# power_supply.net
KiCad netlist of a schematic drawn in Altium Designer
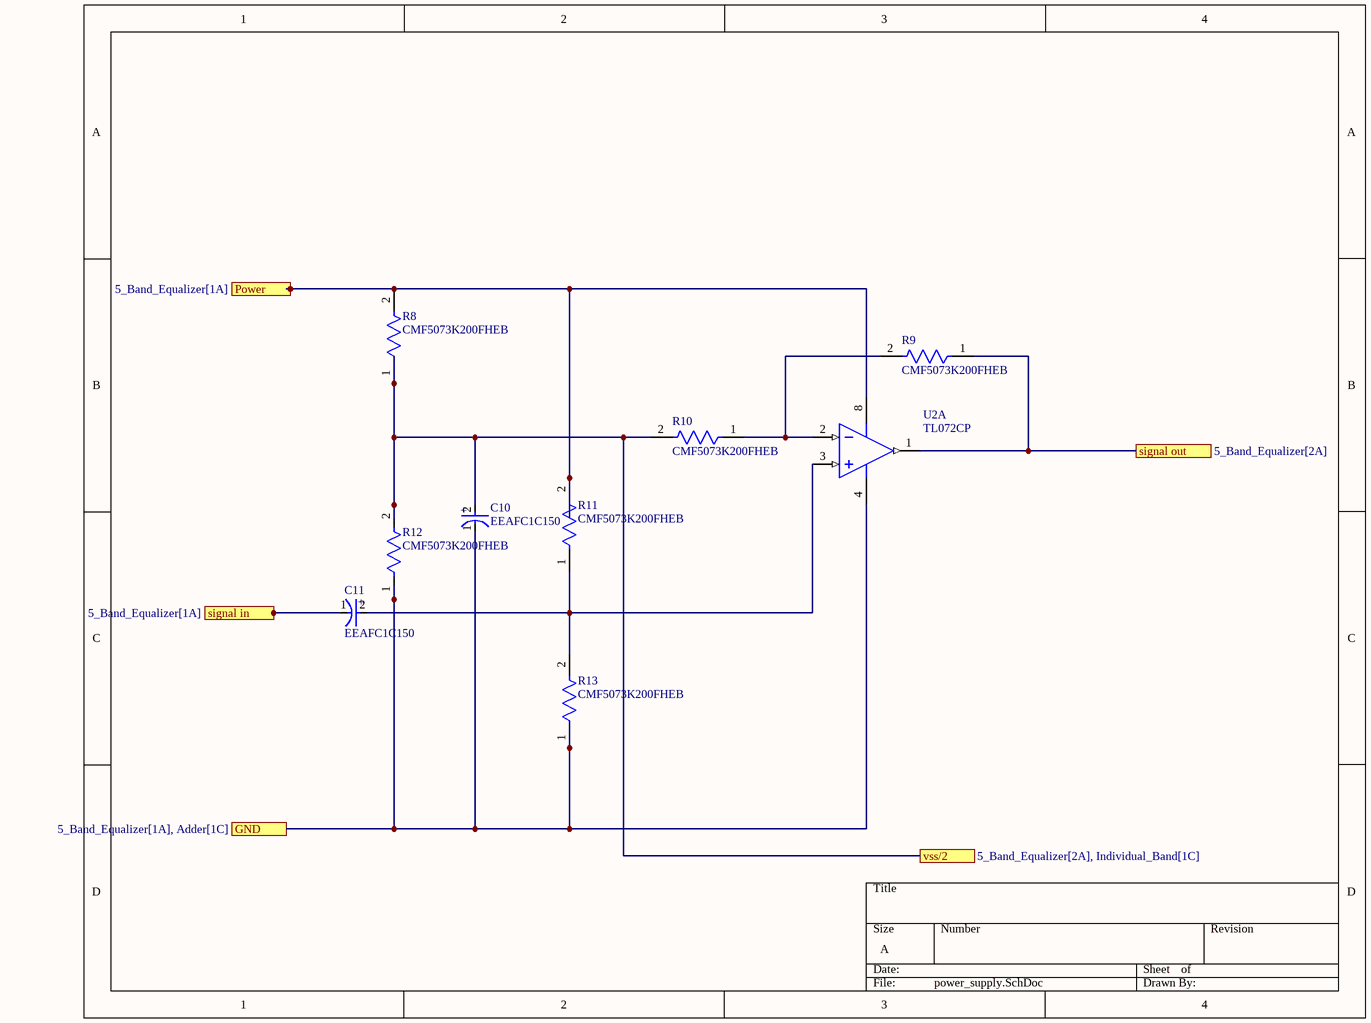
[diagram p0: power_supply.SchDoc]

(export (version "E")
  (design (tool "Eeschema 10.0.6"))
  (components
    (comp (ref "C10")
      (value "EEAFC1C150")
      (footprint "FP-RAD-TH-D_4_0_5-L_7_1-F-MFG")
      (description "Aluminum Electrolytic Capacitors (Radial Lead Type) AEC-Q200 Qualified 15uF ±20% 16V")
      (fields (field (name "VOLTAGE") "16V") (field (name "TOLERANCE") "20%"))
      (libsource (lib "Altium Content Vault") (part "a00bbbee19879c290e62620ae7e47b1"))
    )
    (comp (ref "C11")
      (value "EEAFC1C150")
      (footprint "FP-RAD-TH-D_4_0_5-L_7_1-F-MFG")
      (description "Aluminum Electrolytic Capacitors (Radial Lead Type) AEC-Q200 Qualified 15uF ±20% 16V")
      (fields (field (name "VOLTAGE") "16V") (field (name "TOLERANCE") "20%"))
      (libsource (lib "Altium Content Vault") (part "a00bbbee19879c290e62620ae7e47b1"))
    )
    (comp (ref "R8")
      (value "CMF5073K200FHEB")
      (footprint "FP-CMF50-0")
      (description "CMF5073K200FHEB Res Metal Film 73.2K Ohm 1% 0.125W(1/8W) ±50ppm/°C Epoxy AXL T/R")
      (fields (field (name "TOLERANCE") "1%"))
      (libsource (lib "Altium Content Vault") (part "1029c3af85768c4190bb7ad29bc67b5"))
    )
    (comp (ref "R9")
      (value "CMF5073K200FHEB")
      (footprint "FP-CMF50-0")
      (description "CMF5073K200FHEB Res Metal Film 73.2K Ohm 1% 0.125W(1/8W) ±50ppm/°C Epoxy AXL T/R")
      (fields (field (name "TOLERANCE") "1%"))
      (libsource (lib "Altium Content Vault") (part "1029c3af85768c4190bb7ad29bc67b5"))
    )
    (comp (ref "R10")
      (value "CMF5073K200FHEB")
      (footprint "FP-CMF50-0")
      (description "CMF5073K200FHEB Res Metal Film 73.2K Ohm 1% 0.125W(1/8W) ±50ppm/°C Epoxy AXL T/R")
      (fields (field (name "TOLERANCE") "1%"))
      (libsource (lib "Altium Content Vault") (part "1029c3af85768c4190bb7ad29bc67b5"))
    )
    (comp (ref "R11")
      (value "CMF5073K200FHEB")
      (footprint "FP-CMF50-0")
      (description "CMF5073K200FHEB Res Metal Film 73.2K Ohm 1% 0.125W(1/8W) ±50ppm/°C Epoxy AXL T/R")
      (fields (field (name "TOLERANCE") "1%"))
      (libsource (lib "Altium Content Vault") (part "1029c3af85768c4190bb7ad29bc67b5"))
    )
    (comp (ref "R12")
      (value "CMF5073K200FHEB")
      (footprint "FP-CMF50-0")
      (description "CMF5073K200FHEB Res Metal Film 73.2K Ohm 1% 0.125W(1/8W) ±50ppm/°C Epoxy AXL T/R")
      (fields (field (name "TOLERANCE") "1%"))
      (libsource (lib "Altium Content Vault") (part "1029c3af85768c4190bb7ad29bc67b5"))
    )
    (comp (ref "R13")
      (value "CMF5073K200FHEB")
      (footprint "FP-CMF50-0")
      (description "CMF5073K200FHEB Res Metal Film 73.2K Ohm 1% 0.125W(1/8W) ±50ppm/°C Epoxy AXL T/R")
      (fields (field (name "TOLERANCE") "1%"))
      (libsource (lib "Altium Content Vault") (part "1029c3af85768c4190bb7ad29bc67b5"))
    )
    (comp (ref "U2")
      (value "TL072CP")
      (footprint "P0008A")
      (fields (field (name "MANUFACTURER") "Texas Instruments"))
      (libsource (lib "Altium Content Vault") (part "TI-AMP-D6-2-8_D"))
    )
  )
  (nets
    (net (code "1") (name "/GND") (class "Default")
      (node (ref "C10") (pin "1") (pinfunction "C_1") (pintype "passive"))
      (node (ref "R12") (pin "1") (pinfunction "1_1") (pintype "passive"))
      (node (ref "R13") (pin "1") (pinfunction "1_1") (pintype "passive"))
      (node (ref "U2") (pin "4") (pinfunction "VCC-_4") (pintype "power_in"))
    )
    (net (code "2") (name "/Power") (class "Default")
      (node (ref "R11") (pin "2") (pinfunction "2_2") (pintype "passive"))
      (node (ref "R8") (pin "2") (pinfunction "2_2") (pintype "passive"))
      (node (ref "U2") (pin "8") (pinfunction "VCC+_8") (pintype "power_in"))
    )
    (net (code "3") (name "/signal in") (class "Default")
      (node (ref "C11") (pin "1") (pinfunction "C_1") (pintype "passive"))
    )
    (net (code "4") (name "/signal out") (class "Default")
      (node (ref "R9") (pin "1") (pinfunction "1_1") (pintype "passive"))
      (node (ref "U2") (pin "1") (pinfunction "OUT1_1") (pintype "output"))
    )
    (net (code "5") (name "/vss{slash}2") (class "Default")
      (node (ref "C10") (pin "2") (pinfunction "A_2") (pintype "passive"))
      (node (ref "R10") (pin "2") (pinfunction "2_2") (pintype "passive"))
      (node (ref "R12") (pin "2") (pinfunction "2_2") (pintype "passive"))
      (node (ref "R8") (pin "1") (pinfunction "1_1") (pintype "passive"))
    )
    (net (code "6") (name "Net-(C11-A)") (class "Default")
      (node (ref "C11") (pin "2") (pinfunction "A_2") (pintype "passive"))
      (node (ref "R11") (pin "1") (pinfunction "1_1") (pintype "passive"))
      (node (ref "R13") (pin "2") (pinfunction "2_2") (pintype "passive"))
      (node (ref "U2") (pin "3") (pinfunction "IN1+_3") (pintype "input"))
    )
    (net (code "7") (name "Net-(U2A-IN1-)") (class "Default")
      (node (ref "R10") (pin "1") (pinfunction "1_1") (pintype "passive"))
      (node (ref "R9") (pin "2") (pinfunction "2_2") (pintype "passive"))
      (node (ref "U2") (pin "2") (pinfunction "IN1-_2") (pintype "input"))
    )
  )
)
